# Sheet3.net
KiCad netlist of a schematic drawn in Altium Designer
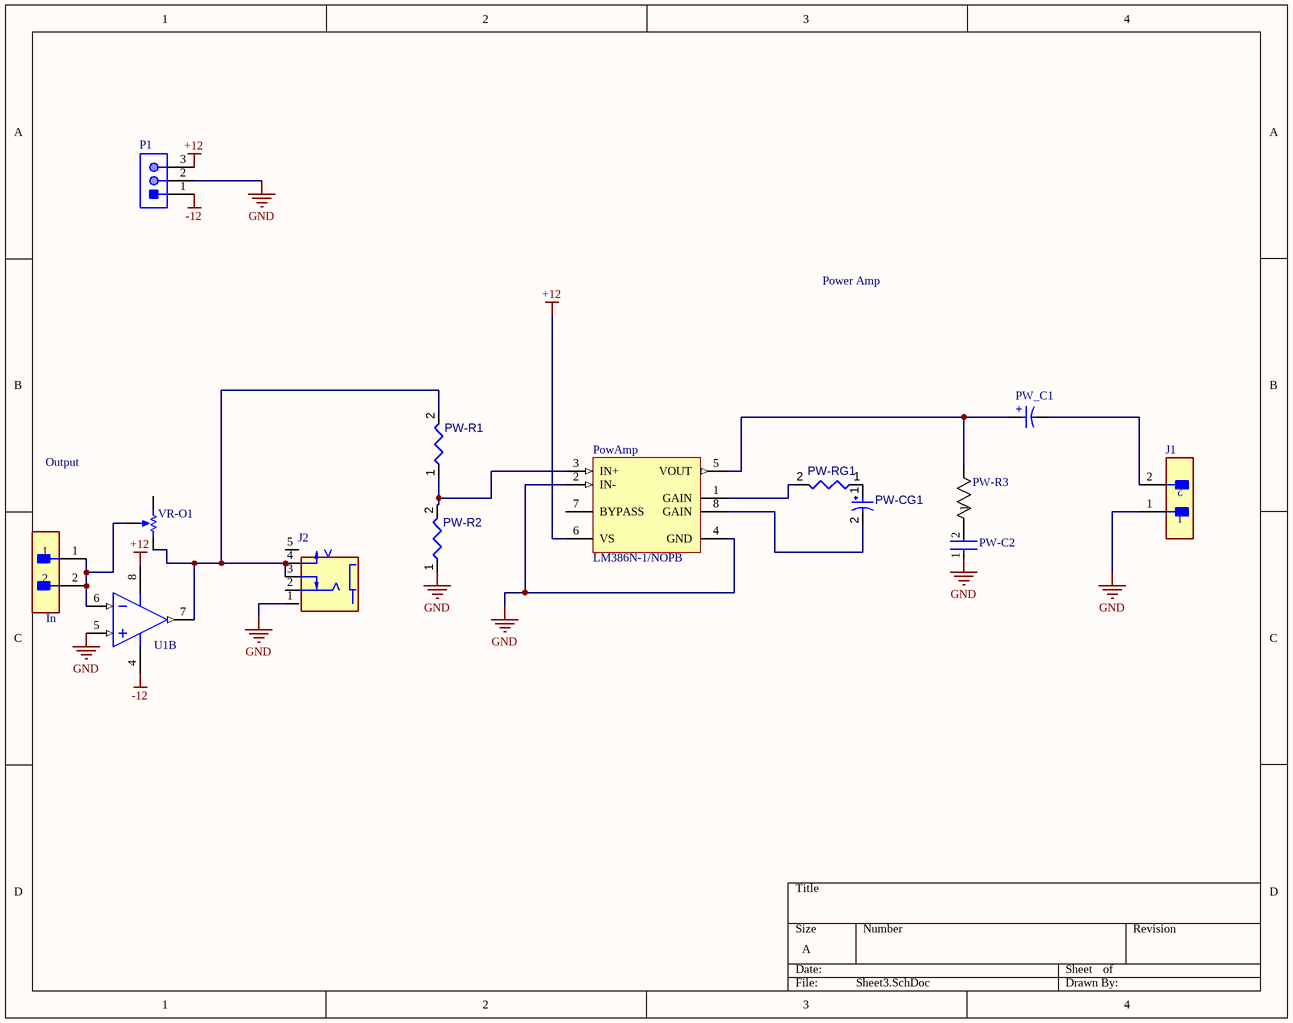
[diagram p0: Sheet3.SchDoc]

(export (version "E")
  (design (tool "Eeschema 10.0.6"))
  (components
    (comp (ref "In")
      (value "TMM-102-03-F-S")
      (footprint "FP-TMM-102-03-F-S-MFG")
      (description "CONN HEADER VERT 2POS 2MM")
      (libsource (lib "") (part "3bc925449376181038e59eaffc5286c_1"))
    )
    (comp (ref "J1")
      (value "TMM-102-03-F-S")
      (footprint "FP-TMM-102-03-F-S-MFG")
      (description "CONN HEADER VERT 2POS 2MM")
      (libsource (lib "Altium Content Vault") (part "3bc925449376181038e59eaffc5286c"))
    )
    (comp (ref "J2")
      (value "35RAPC4BH3")
      (footprint "SWITCHCRAFT_35RAPC4BH3")
      (description "PC horizontal mount Jack stereo threaded bushing 3.5MM, 35 Series ¦ Switchcraft 35RAPC4BH3")
      (fields (field (name "MF") "Switchcraft Inc."))
      (libsource (lib "35RAPC4BH3") (part "35RAPC4BH3"))
    )
    (comp (ref "P1")
      (value "B3P-VH(LF)(SN)")
      (footprint "JST-B3P-VH(LF)(SN)-3_V")
      (fields (field (name "MANUFACTURER") "JST"))
      (libsource (lib "Senuda Ratnayake") (part "CN-1P-M-R3"))
    )
    (comp (ref "PowAmp")
      (value "LM386N-1/NOPB")
      (footprint "P0008A")
      (description "Low Voltage Audio Power Amplifier, 8-pin MDIP, Pb-Free")
      (fields (field (name "MANUFACTURER") "Texas Instruments"))
      (libsource (lib "Altium Content Vault") (part "AMP-APA-LM386-8"))
    )
    (comp (ref "PW-C2")
      (value "VY2102M29Y5US6TV7")
      (footprint "FP-VY2102M29Y5US6TV7-MFG")
      (fields (field (name "VOLTAGE") "300V") (field (name "TOLERANCE") "20%"))
      (libsource (lib "Altium Content Vault") (part "11868f565c42a9108669ba33697ecf6"))
    )
    (comp (ref "PW-CG1")
      (value "ECA1HM100")
      (footprint "CAPPR55-200-1100X500X1200")
      (description "Aluminum Electrolytic Capacitor, 10 uF, +/- 20%, 50 V, -40 to 85 degC, 2-Pin THD, RoHS, Bulk")
      (fields (field (name "MANUFACTURER") "Panasonic") (field (name "TOLERANCE") "20%"))
      (libsource (lib "Senuda Ratnayake") (part "CAP-P-2"))
    )
    (comp (ref "PW-R1")
      (value "MFR-25FBF52-2K21")
      (footprint "RESA60-630X240")
      (description "Axial Resistor, 2.21 KOhm, +/- 1%, 0.25 W, -55 to 155 degC, 2-Pin THD, RoHS, Bulk")
      (fields (field (name "TOLERANCE") "1%") (field (name "POWER") "250mW"))
      (libsource (lib "Senuda Ratnayake") (part "RES-2"))
    )
    (comp (ref "PW-R2")
      (value "MFR-25FBF52-2K21")
      (footprint "RESA60-630X240")
      (description "Axial Resistor, 2.21 KOhm, +/- 1%, 0.25 W, -55 to 155 degC, 2-Pin THD, RoHS, Bulk")
      (fields (field (name "TOLERANCE") "1%") (field (name "POWER") "250mW"))
      (libsource (lib "Senuda Ratnayake") (part "RES-2"))
    )
    (comp (ref "PW-R3")
      (value "AC01000001000JA100")
      (footprint "RES_AC01_VIS")
      (description "VISHAY AC01000001000JA100 Through Hole Resistor, 100 ohm, Axial Leaded, 1 W, 5%, AC Series")
      (fields (field (name "TOLERANCE") "5%"))
      (libsource (lib "Altium Content Vault") (part "AC01000001000JA100"))
    )
    (comp (ref "PW-RG1")
      (value "MFR-25FBF52-2K21")
      (footprint "RESA60-630X240")
      (description "Axial Resistor, 2.21 KOhm, +/- 1%, 0.25 W, -55 to 155 degC, 2-Pin THD, RoHS, Bulk")
      (fields (field (name "TOLERANCE") "1%") (field (name "POWER") "250mW"))
      (libsource (lib "Senuda Ratnayake") (part "RES-2"))
    )
    (comp (ref "PW_C1")
      (value "860240478010")
      (footprint "WCAP-AT1H_D13H25")
      (description "860240478010 WCAP-AT1H Aluminum Electrolytic Capacitors")
      (fields (field (name "TOLERANCE") "20%"))
      (libsource (lib "Altium Content Vault") (part "Capacitor_Polarized"))
    )
    (comp (ref "U1")
      (value "NE5532P")
      (footprint "P0008A")
      (fields (field (name "MANUFACTURER") "Texas Instruments"))
      (libsource (lib "Altium Content Vault") (part "TI-AMP-D6-2-8_D"))
    )
    (comp (ref "VR-O1")
      (value "3852A-282-103AL")
      (footprint "BOUR-3852A-282-103AL-3_V")
      (description "Diameter Panel Control, 10 KOhm, +/- 10%, 2 W, -1 to 125 degC, 3-Pin THD, RoHS, Bulk")
      (fields (field (name "TOLERANCE") "±10%") (field (name "MANUFACTURER") "Bourns"))
      (libsource (lib "Altium Content Vault") (part "RES-POT-3"))
    )
  )
  (nets
    (net (code "1") (name "+12") (class "Default")
      (node (ref "P1") (pin "3") (pinfunction "3_3") (pintype "passive"))
      (node (ref "PowAmp") (pin "6") (pinfunction "VS_6") (pintype "power_in"))
      (node (ref "U1") (pin "8") (pinfunction "VCC+_8") (pintype "power_in"))
    )
    (net (code "2") (name "-12") (class "Default")
      (node (ref "P1") (pin "1") (pinfunction "1_1") (pintype "passive"))
      (node (ref "U1") (pin "4") (pinfunction "VCC-_4") (pintype "power_in"))
    )
    (net (code "3") (name "GND") (class "Default")
      (node (ref "J1") (pin "1") (pinfunction "1_1") (pintype "passive"))
      (node (ref "J2") (pin "1") (pinfunction "1_1") (pintype "passive"))
      (node (ref "P1") (pin "2") (pinfunction "2_2") (pintype "passive"))
      (node (ref "PW-C2") (pin "1") (pinfunction "1_1") (pintype "passive"))
      (node (ref "PW-R2") (pin "1") (pinfunction "1_1") (pintype "passive"))
      (node (ref "PowAmp") (pin "2") (pinfunction "IN-_2") (pintype "input"))
      (node (ref "PowAmp") (pin "4") (pinfunction "GND_4") (pintype "power_in"))
      (node (ref "U1") (pin "5") (pinfunction "IN2+_5") (pintype "input"))
    )
    (net (code "4") (name "Net-(PW-C2-Pad2)") (class "Default")
      (node (ref "PW-C2") (pin "2") (pinfunction "2_2") (pintype "passive"))
      (node (ref "PW-R3") (pin "1") (pinfunction "1_1") (pintype "passive"))
    )
    (net (code "5") (name "Net-(PW-CG1-Pad1)") (class "Default")
      (node (ref "PW-CG1") (pin "1") (pinfunction "1_1") (pintype "passive"))
      (node (ref "PW-RG1") (pin "1") (pinfunction "1_1") (pintype "passive"))
    )
    (net (code "6") (name "Net-(PW-CG1-Pad2)") (class "Default")
      (node (ref "PW-CG1") (pin "2") (pinfunction "2_2") (pintype "passive"))
      (node (ref "PowAmp") (pin "8") (pinfunction "GAIN_8") (pintype "passive"))
    )
    (net (code "7") (name "Net-(PW-RG1-Pad2)") (class "Default")
      (node (ref "PW-RG1") (pin "2") (pinfunction "2_2") (pintype "passive"))
      (node (ref "PowAmp") (pin "1") (pinfunction "GAIN_1") (pintype "passive"))
    )
    (net (code "8") (name "Net-(PW_C1-N)") (class "Default")
      (node (ref "J1") (pin "2") (pinfunction "2_2") (pintype "passive"))
      (node (ref "PW_C1") (pin "2") (pinfunction "N_2") (pintype "passive"))
    )
    (net (code "9") (name "Net-(PW_C1-P)") (class "Default")
      (node (ref "PW-R3") (pin "2") (pinfunction "2_2") (pintype "passive"))
      (node (ref "PW_C1") (pin "1") (pinfunction "P_1") (pintype "passive"))
      (node (ref "PowAmp") (pin "5") (pinfunction "VOUT_5") (pintype "output"))
    )
    (net (code "10") (name "Net-(PowAmp-IN+)") (class "Default")
      (node (ref "PW-R1") (pin "1") (pinfunction "1_1") (pintype "passive"))
      (node (ref "PW-R2") (pin "2") (pinfunction "2_2") (pintype "passive"))
      (node (ref "PowAmp") (pin "3") (pinfunction "IN+_3") (pintype "input"))
    )
    (net (code "11") (name "Net-(U1B-IN2-)") (class "Default")
      (node (ref "In") (pin "1") (pinfunction "1_1") (pintype "passive"))
      (node (ref "In") (pin "2") (pinfunction "2_2") (pintype "passive"))
      (node (ref "U1") (pin "6") (pinfunction "IN2-_6") (pintype "input"))
      (node (ref "VR-O1") (pin "2") (pinfunction "S_2") (pintype "passive"))
    )
    (net (code "12") (name "Net-(U1B-OUT2)") (class "Default")
      (node (ref "J2") (pin "3") (pinfunction "3_3") (pintype "passive"))
      (node (ref "J2") (pin "4") (pinfunction "4_4") (pintype "passive"))
      (node (ref "PW-R1") (pin "2") (pinfunction "2_2") (pintype "passive"))
      (node (ref "U1") (pin "7") (pinfunction "OUT2_7") (pintype "output"))
      (node (ref "VR-O1") (pin "3") (pinfunction "CW_3") (pintype "passive"))
    )
    (net (code "13") (name "unconnected-(J2-Pad2)") (class "Default")
      (node (ref "J2") (pin "2") (pinfunction "2_2") (pintype "passive"))
    )
    (net (code "14") (name "unconnected-(J2-Pad5)") (class "Default")
      (node (ref "J2") (pin "5") (pinfunction "5_5") (pintype "passive"))
    )
    (net (code "15") (name "unconnected-(PowAmp-BYPASS-Pad7)") (class "Default")
      (node (ref "PowAmp") (pin "7") (pinfunction "BYPASS_7") (pintype "passive"))
    )
    (net (code "16") (name "unconnected-(VR-O1-CCW-Pad1)") (class "Default")
      (node (ref "VR-O1") (pin "1") (pinfunction "CCW_1") (pintype "passive"))
    )
  )
)
